# camera_cape.net
KiCad netlist of a schematic drawn in EAGLE
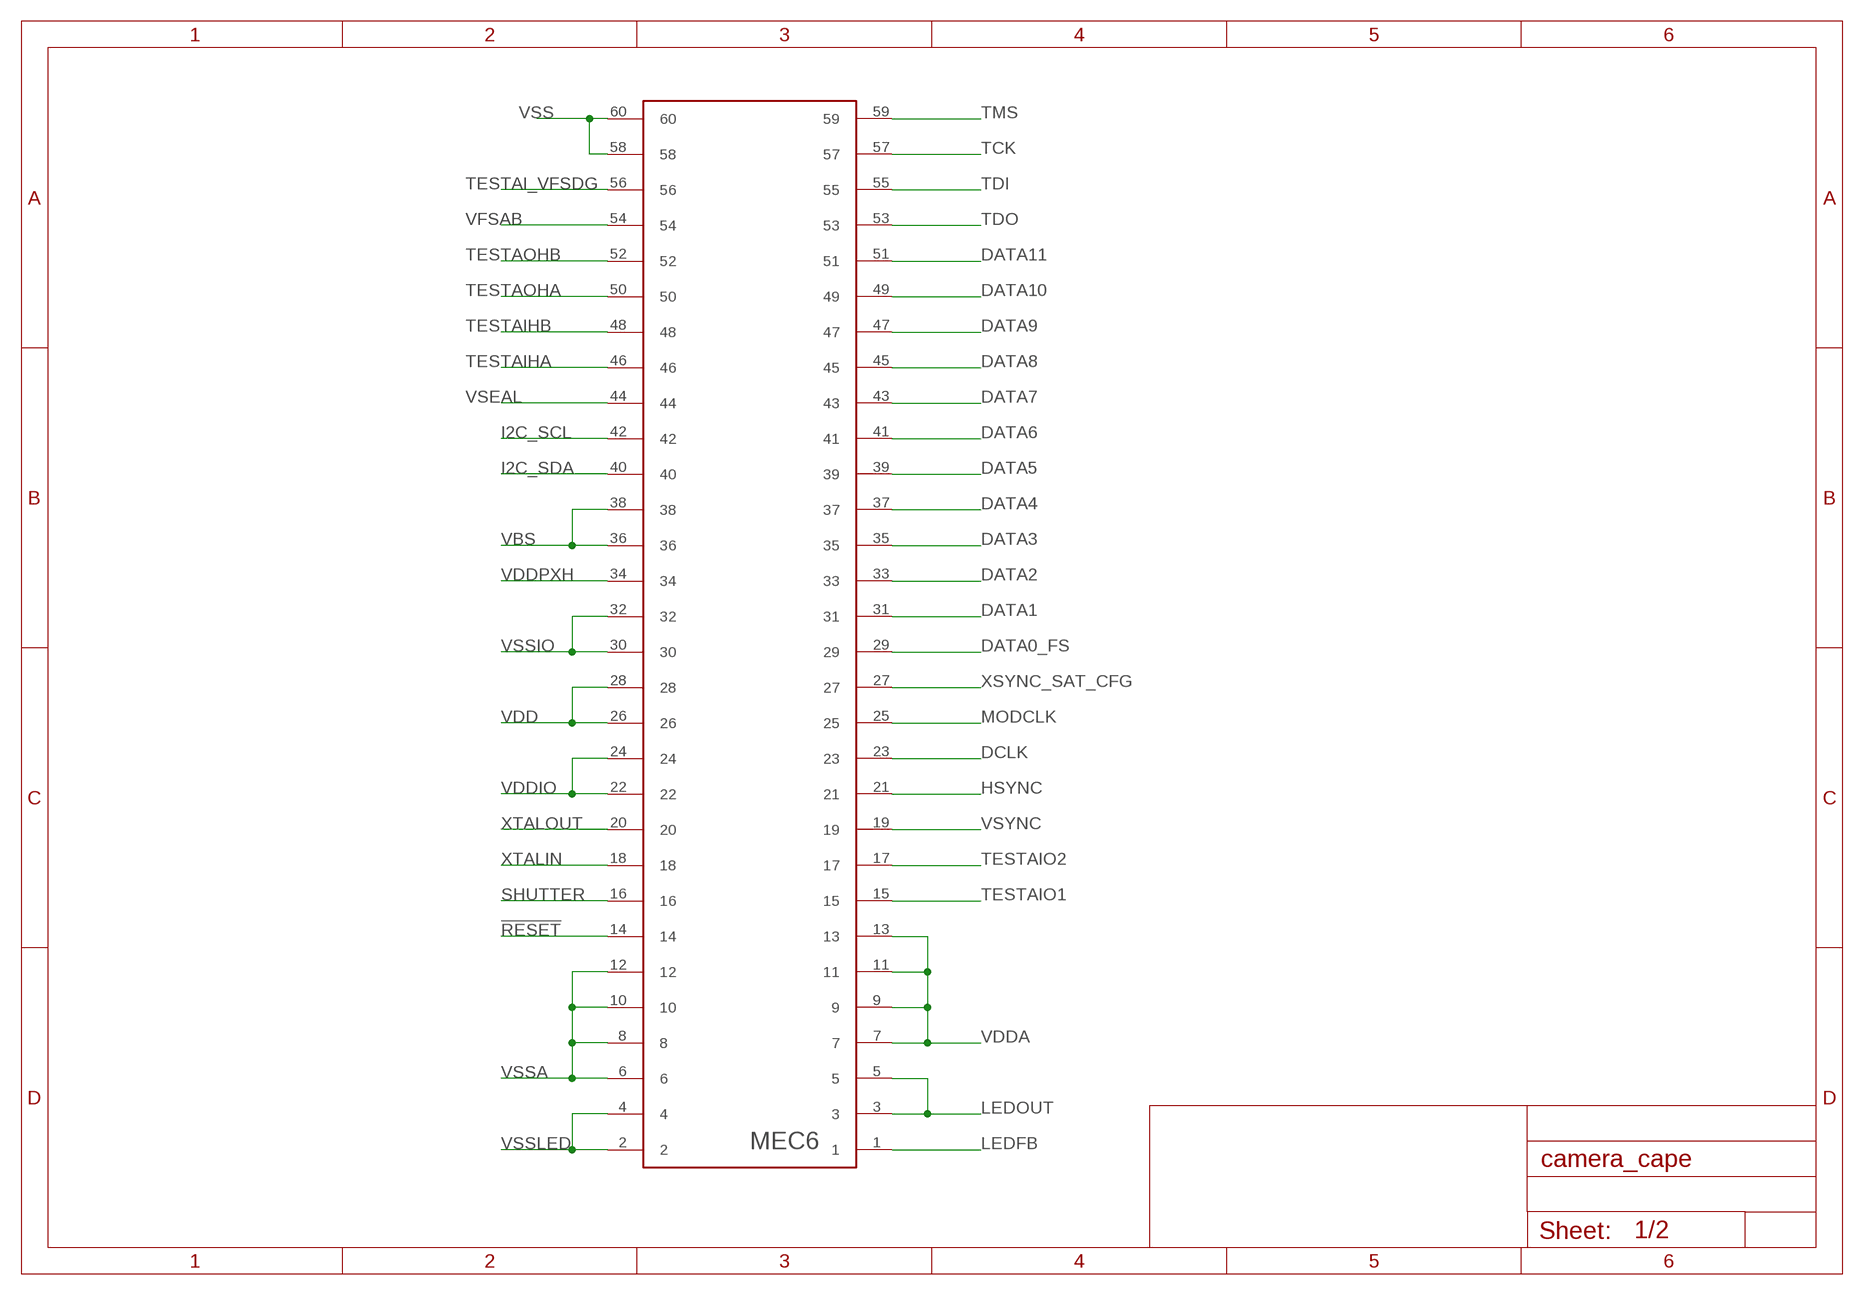
[diagram p0: schematic, sheet 1]
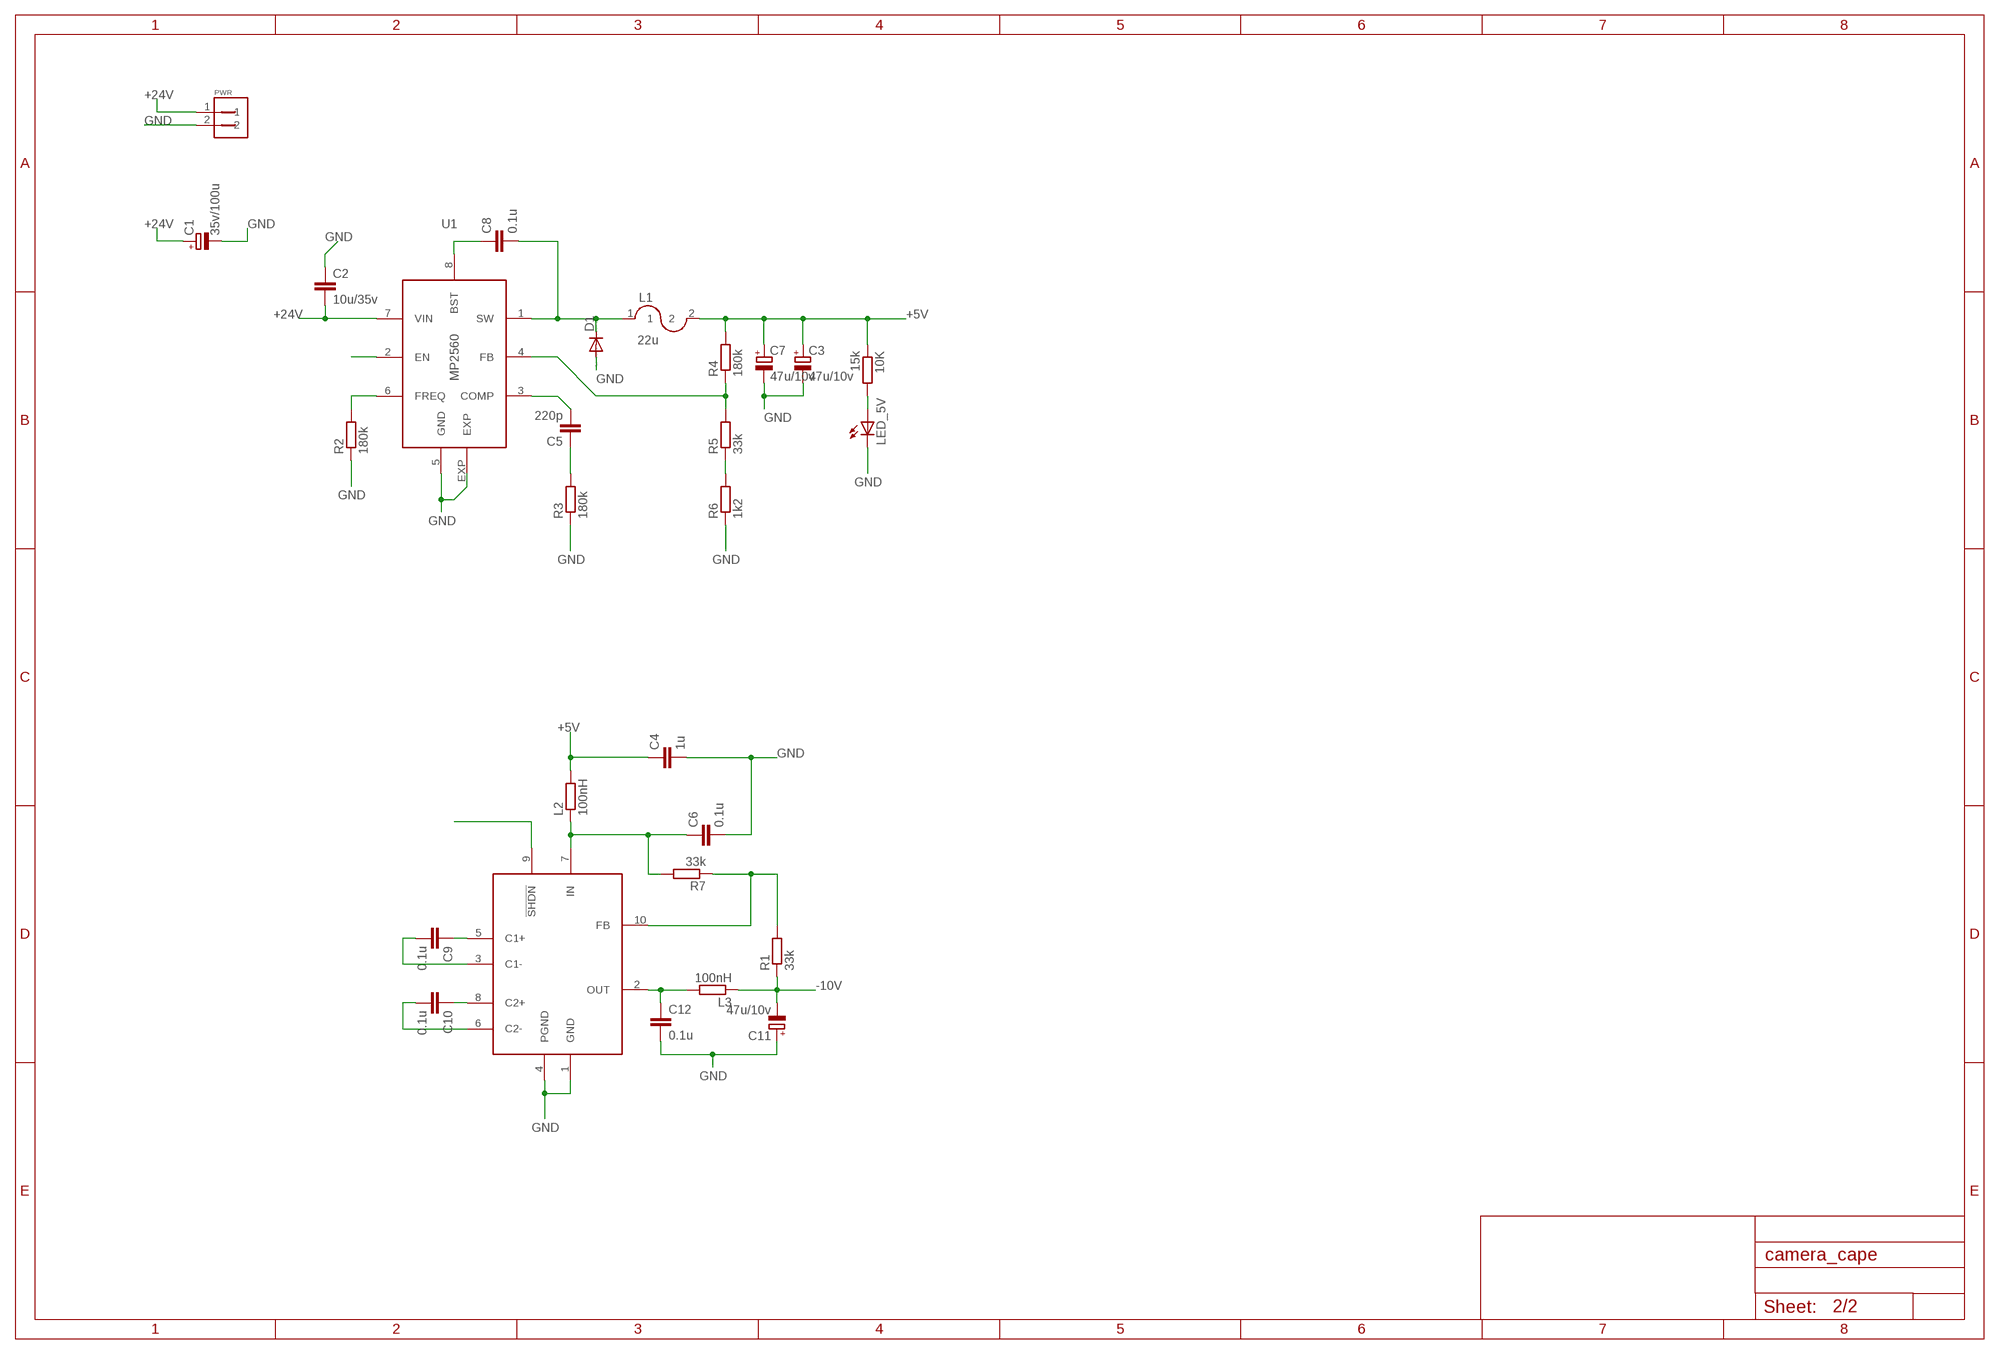
[diagram p1: schematic, sheet 2]

(export (version "E")
  (design (tool "Eeschema 10.0.6"))
  (components
    (comp (ref "10K")
      (value "15k")
      (footprint "eagle-import:R0603")
      (libsource (lib "eagle-import") (part "R-EU_R0603"))
    )
    (comp (ref "C1")
      (value "35v/100u")
      (footprint "eagle-import:150CLZ-0810")
      (libsource (lib "eagle-import") (part "CPOL-EU150CLZ-0810"))
    )
    (comp (ref "C2")
      (value "10u/35v")
      (footprint "eagle-import:C1206")
      (libsource (lib "eagle-import") (part "C-EUC1206"))
    )
    (comp (ref "C3")
      (value "47u/10v")
      (footprint "eagle-import:CT3528")
      (libsource (lib "eagle-import") (part "CPOL-EUCT3528"))
    )
    (comp (ref "C4")
      (value "1u")
      (footprint "eagle-import:C0603")
      (libsource (lib "eagle-import") (part "C-EUC0603"))
    )
    (comp (ref "C5")
      (value "220p")
      (footprint "eagle-import:C0603")
      (libsource (lib "eagle-import") (part "C-EUC0603"))
    )
    (comp (ref "C6")
      (value "0.1u")
      (footprint "eagle-import:C0603")
      (libsource (lib "eagle-import") (part "C-EUC0603"))
    )
    (comp (ref "C7")
      (value "47u/10v")
      (footprint "eagle-import:CT3528")
      (libsource (lib "eagle-import") (part "CPOL-EUCT3528"))
    )
    (comp (ref "C8")
      (value "0.1u")
      (footprint "eagle-import:C0603")
      (libsource (lib "eagle-import") (part "C-EUC0603"))
    )
    (comp (ref "C9")
      (value "0.1u")
      (footprint "eagle-import:C0603")
      (libsource (lib "eagle-import") (part "C-EUC0603"))
    )
    (comp (ref "C10")
      (value "0.1u")
      (footprint "eagle-import:C0603")
      (libsource (lib "eagle-import") (part "C-EUC0603"))
    )
    (comp (ref "C11")
      (value "47u/10v")
      (footprint "eagle-import:CT3528")
      (libsource (lib "eagle-import") (part "CPOL-EUCT3528"))
    )
    (comp (ref "C12")
      (value "0.1u")
      (footprint "eagle-import:C0603")
      (libsource (lib "eagle-import") (part "C-EUC0603"))
    )
    (comp (ref "D1")
      (value "DIODE-DO214AC")
      (footprint "eagle-import:DO214AC")
      (libsource (lib "eagle-import") (part "DIODE-DO214AC"))
    )
    (comp (ref "L1")
      (value "22u")
      (footprint "eagle-import:RCL_L_CDRH8D38")
      (libsource (lib "eagle-import") (part "RCL_L_CDRH8D38"))
    )
    (comp (ref "L2")
      (value "100nH")
      (footprint "eagle-import:R0603")
      (libsource (lib "eagle-import") (part "R-EU_R0603"))
    )
    (comp (ref "L3")
      (value "100nH")
      (footprint "eagle-import:R0603")
      (libsource (lib "eagle-import") (part "R-EU_R0603"))
    )
    (comp (ref "LED_5V")
      (value "LEDSML0603")
      (footprint "eagle-import:SML0603")
      (libsource (lib "eagle-import") (part "LEDSML0603"))
    )
    (comp (ref "PWR")
      (value "CON_MOLEX_MINIFIT_2190")
      (footprint "eagle-import:CON_MOLEX_MINIFIT_2_1")
      (libsource (lib "eagle-import") (part "CON_MOLEX_MINIFIT_2190"))
    )
    (comp (ref "R1")
      (value "33k")
      (footprint "eagle-import:R0603")
      (libsource (lib "eagle-import") (part "R-EU_R0603"))
    )
    (comp (ref "R2")
      (value "180k")
      (footprint "eagle-import:R0603")
      (libsource (lib "eagle-import") (part "R-EU_R0603"))
    )
    (comp (ref "R3")
      (value "180k")
      (footprint "eagle-import:R0603")
      (libsource (lib "eagle-import") (part "R-EU_R0603"))
    )
    (comp (ref "R4")
      (value "180k")
      (footprint "eagle-import:R0603")
      (libsource (lib "eagle-import") (part "R-EU_R0603"))
    )
    (comp (ref "R5")
      (value "33k")
      (footprint "eagle-import:R0603")
      (libsource (lib "eagle-import") (part "R-EU_R0603"))
    )
    (comp (ref "R6")
      (value "1k2")
      (footprint "eagle-import:R0603")
      (libsource (lib "eagle-import") (part "R-EU_R0603"))
    )
    (comp (ref "R7")
      (value "33k")
      (footprint "eagle-import:R0603")
      (libsource (lib "eagle-import") (part "R-EU_R0603"))
    )
    (comp (ref "U$1")
      (value "MAX868")
      (footprint "eagle-import:UMAX_10PIN")
      (libsource (lib "eagle-import") (part "MAX868"))
    )
    (comp (ref "U1")
      (value "MP2560")
      (footprint "eagle-import:SOIC-8E")
      (libsource (lib "eagle-import") (part "MP2560"))
    )
    (comp (ref "J1")
      (value "MEC6")
      (footprint "eagle-import:MEC6-130-02-X-D-RA1")
      (libsource (lib "eagle-import") (part "MEC6"))
    )
  )
  (nets
    (net (code "1") (name "+5V") (class "Default")
      (node (ref "10K") (pin "1") (pinfunction "1_1") (pintype "passive"))
      (node (ref "C3") (pin "+") (pinfunction "+_+") (pintype "passive"))
      (node (ref "C4") (pin "1") (pinfunction "1_1") (pintype "passive"))
      (node (ref "C7") (pin "+") (pinfunction "+_+") (pintype "passive"))
      (node (ref "L1") (pin "2") (pinfunction "2_2") (pintype "bidirectional"))
      (node (ref "L2") (pin "2") (pinfunction "2_2") (pintype "passive"))
      (node (ref "R4") (pin "2") (pinfunction "2_2") (pintype "passive"))
    )
    (net (code "2") (name "+24V") (class "Default")
      (node (ref "C1") (pin "+") (pinfunction "+_+") (pintype "passive"))
      (node (ref "C2") (pin "2") (pinfunction "2_2") (pintype "passive"))
      (node (ref "PWR") (pin "1") (pinfunction "1_1") (pintype "passive"))
      (node (ref "U1") (pin "7") (pinfunction "VIN_7") (pintype "bidirectional"))
    )
    (net (code "3") (name "-10V") (class "Default")
      (node (ref "C11") (pin "-") (pinfunction "-_-") (pintype "passive"))
      (node (ref "L3") (pin "1") (pinfunction "1_1") (pintype "passive"))
      (node (ref "R1") (pin "1") (pinfunction "1_1") (pintype "passive"))
    )
    (net (code "4") (name "DATA0_FS") (class "Default")
      (node (ref "J1") (pin "29") (pinfunction "29_29") (pintype "bidirectional"))
    )
    (net (code "5") (name "DATA1") (class "Default")
      (node (ref "J1") (pin "31") (pinfunction "31_31") (pintype "bidirectional"))
    )
    (net (code "6") (name "DATA2") (class "Default")
      (node (ref "J1") (pin "33") (pinfunction "33_33") (pintype "bidirectional"))
    )
    (net (code "7") (name "DATA3") (class "Default")
      (node (ref "J1") (pin "35") (pinfunction "35_35") (pintype "bidirectional"))
    )
    (net (code "8") (name "DATA4") (class "Default")
      (node (ref "J1") (pin "37") (pinfunction "37_37") (pintype "bidirectional"))
    )
    (net (code "9") (name "DATA5") (class "Default")
      (node (ref "J1") (pin "39") (pinfunction "39_39") (pintype "bidirectional"))
    )
    (net (code "10") (name "DATA6") (class "Default")
      (node (ref "J1") (pin "41") (pinfunction "41_41") (pintype "bidirectional"))
    )
    (net (code "11") (name "DATA7") (class "Default")
      (node (ref "J1") (pin "43") (pinfunction "43_43") (pintype "bidirectional"))
    )
    (net (code "12") (name "DATA8") (class "Default")
      (node (ref "J1") (pin "45") (pinfunction "45_45") (pintype "bidirectional"))
    )
    (net (code "13") (name "DATA9") (class "Default")
      (node (ref "J1") (pin "47") (pinfunction "47_47") (pintype "bidirectional"))
    )
    (net (code "14") (name "DATA10") (class "Default")
      (node (ref "J1") (pin "49") (pinfunction "49_49") (pintype "bidirectional"))
    )
    (net (code "15") (name "DATA11") (class "Default")
      (node (ref "J1") (pin "51") (pinfunction "51_51") (pintype "bidirectional"))
    )
    (net (code "16") (name "DCLK") (class "Default")
      (node (ref "J1") (pin "23") (pinfunction "23_23") (pintype "bidirectional"))
    )
    (net (code "17") (name "GND") (class "Default")
      (node (ref "C1") (pin "-") (pinfunction "-_-") (pintype "passive"))
      (node (ref "C11") (pin "+") (pinfunction "+_+") (pintype "passive"))
      (node (ref "C12") (pin "2") (pinfunction "2_2") (pintype "passive"))
      (node (ref "C2") (pin "1") (pinfunction "1_1") (pintype "passive"))
      (node (ref "C3") (pin "-") (pinfunction "-_-") (pintype "passive"))
      (node (ref "C4") (pin "2") (pinfunction "2_2") (pintype "passive"))
      (node (ref "C6") (pin "2") (pinfunction "2_2") (pintype "passive"))
      (node (ref "C7") (pin "-") (pinfunction "-_-") (pintype "passive"))
      (node (ref "D1") (pin "A") (pinfunction "A_A") (pintype "passive"))
      (node (ref "LED_5V") (pin "C") (pinfunction "C_C") (pintype "passive"))
      (node (ref "PWR") (pin "2") (pinfunction "2_2") (pintype "passive"))
      (node (ref "R2") (pin "1") (pinfunction "1_1") (pintype "passive"))
      (node (ref "R3") (pin "1") (pinfunction "1_1") (pintype "passive"))
      (node (ref "R6") (pin "1") (pinfunction "1_1") (pintype "passive"))
      (node (ref "U$1") (pin "1") (pinfunction "GND_1") (pintype "bidirectional"))
      (node (ref "U$1") (pin "4") (pinfunction "PGND_4") (pintype "bidirectional"))
      (node (ref "U1") (pin "5") (pinfunction "GND_5") (pintype "bidirectional"))
      (node (ref "U1") (pin "EXP") (pinfunction "EXP_EXP") (pintype "bidirectional"))
    )
    (net (code "18") (name "HSYNC") (class "Default")
      (node (ref "J1") (pin "21") (pinfunction "21_21") (pintype "bidirectional"))
    )
    (net (code "19") (name "I2C_SCL") (class "Default")
      (node (ref "J1") (pin "42") (pinfunction "42_42") (pintype "bidirectional"))
    )
    (net (code "20") (name "I2C_SDA") (class "Default")
      (node (ref "J1") (pin "40") (pinfunction "40_40") (pintype "bidirectional"))
    )
    (net (code "21") (name "LEDFB") (class "Default")
      (node (ref "J1") (pin "1") (pinfunction "1_1") (pintype "bidirectional"))
    )
    (net (code "22") (name "LEDOUT") (class "Default")
      (node (ref "J1") (pin "3") (pinfunction "3_3") (pintype "bidirectional"))
      (node (ref "J1") (pin "5") (pinfunction "5_5") (pintype "bidirectional"))
    )
    (net (code "23") (name "MODCLK") (class "Default")
      (node (ref "J1") (pin "25") (pinfunction "25_25") (pintype "bidirectional"))
    )
    (net (code "24") (name "Net-(10K-Pad2)") (class "Default")
      (node (ref "10K") (pin "2") (pinfunction "2_2") (pintype "passive"))
      (node (ref "LED_5V") (pin "A") (pinfunction "A_A") (pintype "passive"))
    )
    (net (code "25") (name "Net-(C5-Pad1)") (class "Default")
      (node (ref "C5") (pin "1") (pinfunction "1_1") (pintype "passive"))
      (node (ref "R3") (pin "2") (pinfunction "2_2") (pintype "passive"))
    )
    (net (code "26") (name "Net-(R5-Pad1)") (class "Default")
      (node (ref "R5") (pin "1") (pinfunction "1_1") (pintype "passive"))
      (node (ref "R6") (pin "2") (pinfunction "2_2") (pintype "passive"))
    )
    (net (code "27") (name "Net-(U$1-C1+)") (class "Default")
      (node (ref "C9") (pin "1") (pinfunction "1_1") (pintype "passive"))
      (node (ref "U$1") (pin "5") (pinfunction "C1+_5") (pintype "bidirectional"))
    )
    (net (code "28") (name "Net-(U$1-C1-)") (class "Default")
      (node (ref "C9") (pin "2") (pinfunction "2_2") (pintype "passive"))
      (node (ref "U$1") (pin "3") (pinfunction "C1-_3") (pintype "bidirectional"))
    )
    (net (code "29") (name "Net-(U$1-C2+)") (class "Default")
      (node (ref "C10") (pin "1") (pinfunction "1_1") (pintype "passive"))
      (node (ref "U$1") (pin "8") (pinfunction "C2+_8") (pintype "bidirectional"))
    )
    (net (code "30") (name "Net-(U$1-C2-)") (class "Default")
      (node (ref "C10") (pin "2") (pinfunction "2_2") (pintype "passive"))
      (node (ref "U$1") (pin "6") (pinfunction "C2-_6") (pintype "bidirectional"))
    )
    (net (code "31") (name "Net-(U$1-FB)") (class "Default")
      (node (ref "R1") (pin "2") (pinfunction "2_2") (pintype "passive"))
      (node (ref "R7") (pin "1") (pinfunction "1_1") (pintype "passive"))
      (node (ref "U$1") (pin "10") (pinfunction "FB_10") (pintype "bidirectional"))
    )
    (net (code "32") (name "Net-(U$1-IN)") (class "Default")
      (node (ref "C6") (pin "1") (pinfunction "1_1") (pintype "passive"))
      (node (ref "L2") (pin "1") (pinfunction "1_1") (pintype "passive"))
      (node (ref "R7") (pin "2") (pinfunction "2_2") (pintype "passive"))
      (node (ref "U$1") (pin "7") (pinfunction "IN_7") (pintype "bidirectional"))
    )
    (net (code "33") (name "Net-(U$1-OUT)") (class "Default")
      (node (ref "C12") (pin "1") (pinfunction "1_1") (pintype "passive"))
      (node (ref "L3") (pin "2") (pinfunction "2_2") (pintype "passive"))
      (node (ref "U$1") (pin "2") (pinfunction "OUT_2") (pintype "bidirectional"))
    )
    (net (code "34") (name "Net-(U1-BST)") (class "Default")
      (node (ref "C8") (pin "1") (pinfunction "1_1") (pintype "passive"))
      (node (ref "U1") (pin "8") (pinfunction "BST_8") (pintype "bidirectional"))
    )
    (net (code "35") (name "Net-(U1-COMP)") (class "Default")
      (node (ref "C5") (pin "2") (pinfunction "2_2") (pintype "passive"))
      (node (ref "U1") (pin "3") (pinfunction "COMP_3") (pintype "bidirectional"))
    )
    (net (code "36") (name "Net-(U1-FB)") (class "Default")
      (node (ref "R4") (pin "1") (pinfunction "1_1") (pintype "passive"))
      (node (ref "R5") (pin "2") (pinfunction "2_2") (pintype "passive"))
      (node (ref "U1") (pin "4") (pinfunction "FB_4") (pintype "bidirectional"))
    )
    (net (code "37") (name "Net-(U1-FREQ)") (class "Default")
      (node (ref "R2") (pin "2") (pinfunction "2_2") (pintype "passive"))
      (node (ref "U1") (pin "6") (pinfunction "FREQ_6") (pintype "bidirectional"))
    )
    (net (code "38") (name "Net-(U1-SW)") (class "Default")
      (node (ref "C8") (pin "2") (pinfunction "2_2") (pintype "passive"))
      (node (ref "D1") (pin "C") (pinfunction "C_C") (pintype "passive"))
      (node (ref "L1") (pin "1") (pinfunction "1_1") (pintype "bidirectional"))
      (node (ref "U1") (pin "1") (pinfunction "SW_1") (pintype "bidirectional"))
    )
    (net (code "39") (name "SHUTTER") (class "Default")
      (node (ref "J1") (pin "16") (pinfunction "16_16") (pintype "bidirectional"))
    )
    (net (code "40") (name "TCK") (class "Default")
      (node (ref "J1") (pin "57") (pinfunction "57_57") (pintype "bidirectional"))
    )
    (net (code "41") (name "TDI") (class "Default")
      (node (ref "J1") (pin "55") (pinfunction "55_55") (pintype "bidirectional"))
    )
    (net (code "42") (name "TDO") (class "Default")
      (node (ref "J1") (pin "53") (pinfunction "53_53") (pintype "bidirectional"))
    )
    (net (code "43") (name "TESTAIHA") (class "Default")
      (node (ref "J1") (pin "46") (pinfunction "46_46") (pintype "bidirectional"))
    )
    (net (code "44") (name "TESTAIHB") (class "Default")
      (node (ref "J1") (pin "48") (pinfunction "48_48") (pintype "bidirectional"))
    )
    (net (code "45") (name "TESTAIO1") (class "Default")
      (node (ref "J1") (pin "15") (pinfunction "15_15") (pintype "bidirectional"))
    )
    (net (code "46") (name "TESTAIO2") (class "Default")
      (node (ref "J1") (pin "17") (pinfunction "17_17") (pintype "bidirectional"))
    )
    (net (code "47") (name "TESTAI_VFSDG") (class "Default")
      (node (ref "J1") (pin "56") (pinfunction "56_56") (pintype "bidirectional"))
    )
    (net (code "48") (name "TESTAOHA") (class "Default")
      (node (ref "J1") (pin "50") (pinfunction "50_50") (pintype "bidirectional"))
    )
    (net (code "49") (name "TESTAOHB") (class "Default")
      (node (ref "J1") (pin "52") (pinfunction "52_52") (pintype "bidirectional"))
    )
    (net (code "50") (name "TMS") (class "Default")
      (node (ref "J1") (pin "59") (pinfunction "59_59") (pintype "bidirectional"))
    )
    (net (code "51") (name "VBS") (class "Default")
      (node (ref "J1") (pin "36") (pinfunction "36_36") (pintype "bidirectional"))
      (node (ref "J1") (pin "38") (pinfunction "38_38") (pintype "bidirectional"))
    )
    (net (code "52") (name "VDD") (class "Default")
      (node (ref "J1") (pin "26") (pinfunction "26_26") (pintype "bidirectional"))
      (node (ref "J1") (pin "28") (pinfunction "28_28") (pintype "bidirectional"))
    )
    (net (code "53") (name "VDDA") (class "Default")
      (node (ref "J1") (pin "11") (pinfunction "11_11") (pintype "bidirectional"))
      (node (ref "J1") (pin "13") (pinfunction "13_13") (pintype "bidirectional"))
      (node (ref "J1") (pin "7") (pinfunction "7_7") (pintype "bidirectional"))
      (node (ref "J1") (pin "9") (pinfunction "9_9") (pintype "bidirectional"))
    )
    (net (code "54") (name "VDDIO") (class "Default")
      (node (ref "J1") (pin "22") (pinfunction "22_22") (pintype "bidirectional"))
      (node (ref "J1") (pin "24") (pinfunction "24_24") (pintype "bidirectional"))
    )
    (net (code "55") (name "VDDPXH") (class "Default")
      (node (ref "J1") (pin "34") (pinfunction "34_34") (pintype "bidirectional"))
    )
    (net (code "56") (name "VFSAB") (class "Default")
      (node (ref "J1") (pin "54") (pinfunction "54_54") (pintype "bidirectional"))
    )
    (net (code "57") (name "VSEAL") (class "Default")
      (node (ref "J1") (pin "44") (pinfunction "44_44") (pintype "bidirectional"))
    )
    (net (code "58") (name "VSS") (class "Default")
      (node (ref "J1") (pin "58") (pinfunction "58_58") (pintype "bidirectional"))
      (node (ref "J1") (pin "60") (pinfunction "60_60") (pintype "bidirectional"))
    )
    (net (code "59") (name "VSSA") (class "Default")
      (node (ref "J1") (pin "10") (pinfunction "10_10") (pintype "bidirectional"))
      (node (ref "J1") (pin "12") (pinfunction "12_12") (pintype "bidirectional"))
      (node (ref "J1") (pin "6") (pinfunction "6_6") (pintype "bidirectional"))
      (node (ref "J1") (pin "8") (pinfunction "8_8") (pintype "bidirectional"))
    )
    (net (code "60") (name "VSSIO") (class "Default")
      (node (ref "J1") (pin "30") (pinfunction "30_30") (pintype "bidirectional"))
      (node (ref "J1") (pin "32") (pinfunction "32_32") (pintype "bidirectional"))
    )
    (net (code "61") (name "VSSLED") (class "Default")
      (node (ref "J1") (pin "2") (pinfunction "2_2") (pintype "bidirectional"))
      (node (ref "J1") (pin "4") (pinfunction "4_4") (pintype "bidirectional"))
    )
    (net (code "62") (name "VSYNC") (class "Default")
      (node (ref "J1") (pin "19") (pinfunction "19_19") (pintype "bidirectional"))
    )
    (net (code "63") (name "XSYNC_SAT_CFG") (class "Default")
      (node (ref "J1") (pin "27") (pinfunction "27_27") (pintype "bidirectional"))
    )
    (net (code "64") (name "XTALIN") (class "Default")
      (node (ref "J1") (pin "18") (pinfunction "18_18") (pintype "bidirectional"))
    )
    (net (code "65") (name "XTALOUT") (class "Default")
      (node (ref "J1") (pin "20") (pinfunction "20_20") (pintype "bidirectional"))
    )
    (net (code "66") (name "unconnected-(U$1-~{SHDN}-Pad9)") (class "Default")
      (node (ref "U$1") (pin "9") (pinfunction "~{SHDN}_9") (pintype "bidirectional"))
    )
    (net (code "67") (name "unconnected-(U1-EN-Pad2)") (class "Default")
      (node (ref "U1") (pin "2") (pinfunction "EN_2") (pintype "bidirectional"))
    )
    (net (code "68") (name "~{RESET}") (class "Default")
      (node (ref "J1") (pin "14") (pinfunction "14_14") (pintype "bidirectional"))
    )
  )
)
